# Thermocouple_Channel.net
KiCad netlist of a schematic drawn in Altium Designer
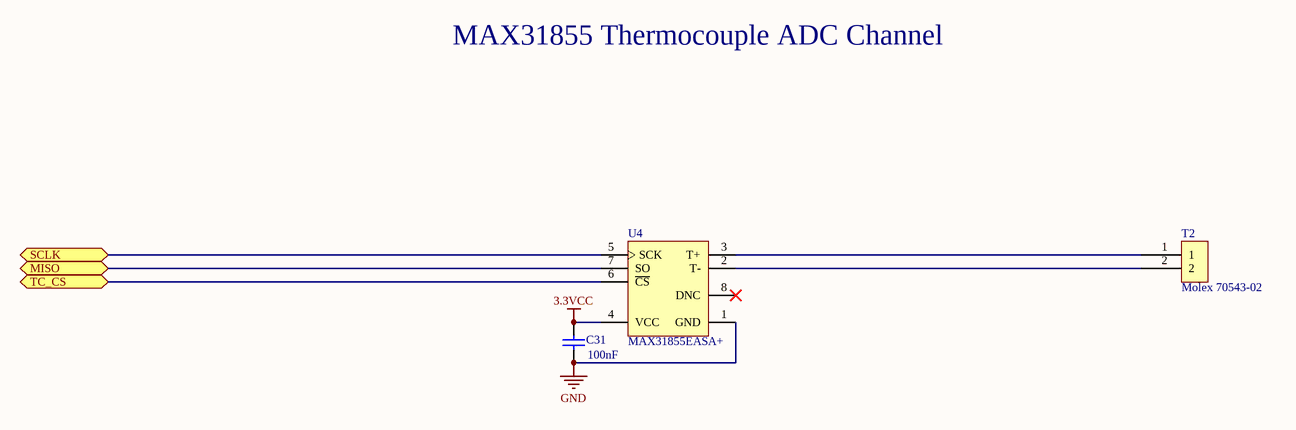
[diagram p0: Thermocouple Channel.SchDoc]

(export (version "E")
  (design (tool "Eeschema 10.0.6"))
  (components
    (comp (ref "C31")
      (value "100nF")
      (footprint "1608[0603]")
      (description "Capacitor (Semiconductor SIM Model)")
      (fields (field (name "Comment") "Cap Semi") (field (name "PUBLISHER") "Altium Limited"))
      (libsource (lib "Miscellaneous Devices") (part "Cap Semi"))
    )
    (comp (ref "T2")
      (value "Molex 70543-02")
      (footprint "70543-02")
      (libsource (lib "ZMBo Schematic Library") (part "Molex 70543-02"))
    )
    (comp (ref "U4")
      (value "MAX31855EASA+")
      (footprint "MAXM-S8+4_N")
      (fields (field (name "GENERIC PART NUMBER") "MAX31855"))
      (libsource (lib "Maxim Sensors") (part "MAX31855EASA+"))
    )
  )
  (nets
    (net (code "1") (name "/MISO") (class "Default")
      (node (ref "U4") (pin "7") (pinfunction "SO_7") (pintype "passive"))
    )
    (net (code "2") (name "/SCLK") (class "Default")
      (node (ref "U4") (pin "5") (pinfunction "SCK_5") (pintype "passive"))
    )
    (net (code "3") (name "/TC_CS") (class "Default")
      (node (ref "U4") (pin "6") (pinfunction "~{CS}_6") (pintype "passive"))
    )
    (net (code "4") (name "3.3VCC") (class "Default")
      (node (ref "C31") (pin "2") (pinfunction "2_2") (pintype "passive"))
      (node (ref "U4") (pin "4") (pinfunction "VCC_4") (pintype "power_in"))
    )
    (net (code "5") (name "GND") (class "Default")
      (node (ref "C31") (pin "1") (pinfunction "1_1") (pintype "passive"))
      (node (ref "U4") (pin "1") (pinfunction "GND_1") (pintype "passive"))
    )
    (net (code "6") (name "Net-(U4-T+)") (class "Default")
      (node (ref "T2") (pin "1") (pinfunction "1_1") (pintype "passive"))
      (node (ref "U4") (pin "3") (pinfunction "T+_3") (pintype "passive"))
    )
    (net (code "7") (name "Net-(U4-T-)") (class "Default")
      (node (ref "T2") (pin "2") (pinfunction "2_2") (pintype "passive"))
      (node (ref "U4") (pin "2") (pinfunction "T-_2") (pintype "passive"))
    )
    (net (code "8") (name "unconnected-(U4-DNC-Pad8)") (class "Default")
      (node (ref "U4") (pin "8") (pinfunction "DNC_8") (pintype "passive+no_connect"))
    )
  )
)
